# schematic.net
KiCad netlist of a schematic drawn in EAGLE
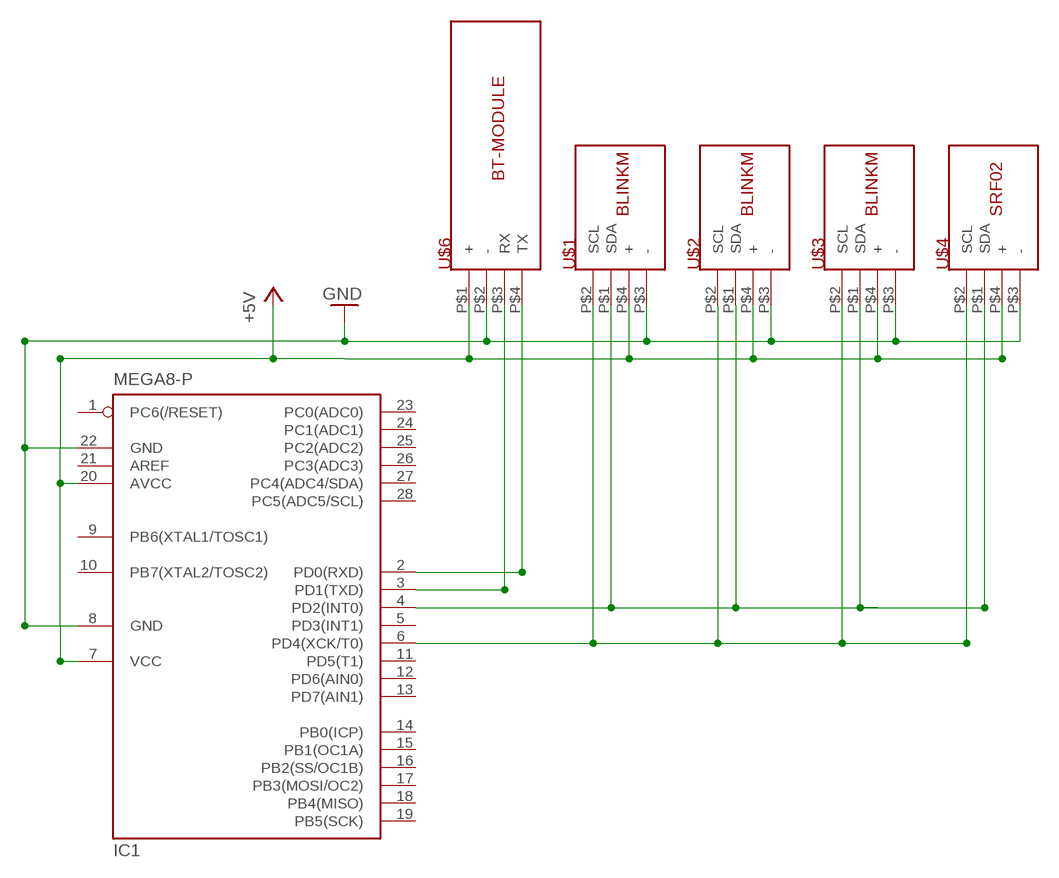
[diagram p0: schematic, sheet 1]

(export (version "E")
  (design (tool "Eeschema 10.0.6"))
  (components
    (comp (ref "IC1")
      (value "MEGA8-P")
      (footprint "eagle-import:DIL28-3")
      (libsource (lib "eagle-import") (part "MEGA8-P"))
    )
    (comp (ref "U$1")
      (value "BLINKM")
      (footprint "eagle-import:BLINKM")
      (libsource (lib "eagle-import") (part "BLINKM"))
    )
    (comp (ref "U$2")
      (value "BLINKM")
      (footprint "eagle-import:BLINKM")
      (libsource (lib "eagle-import") (part "BLINKM"))
    )
    (comp (ref "U$3")
      (value "BLINKM")
      (footprint "eagle-import:BLINKM")
      (libsource (lib "eagle-import") (part "BLINKM"))
    )
    (comp (ref "U$4")
      (value "SRF02")
      (footprint "eagle-import:BLINKM")
      (libsource (lib "eagle-import") (part "BLINKM"))
    )
    (comp (ref "U$6")
      (value "BT-MODULE")
      (footprint "eagle-import:BT-MODULE")
      (libsource (lib "eagle-import") (part "BT-MODULE"))
    )
  )
  (nets
    (net (code "1") (name "+5V") (class "Default")
      (node (ref "IC1") (pin "20") (pinfunction "AVCC_20") (pintype "power_in"))
      (node (ref "IC1") (pin "7") (pinfunction "VCC_7") (pintype "power_in"))
      (node (ref "U$1") (pin "P$4") (pinfunction "+_P$4") (pintype "bidirectional"))
      (node (ref "U$2") (pin "P$4") (pinfunction "+_P$4") (pintype "bidirectional"))
      (node (ref "U$3") (pin "P$4") (pinfunction "+_P$4") (pintype "bidirectional"))
      (node (ref "U$4") (pin "P$4") (pinfunction "+_P$4") (pintype "bidirectional"))
      (node (ref "U$6") (pin "P$1") (pinfunction "+_P$1") (pintype "bidirectional"))
    )
    (net (code "2") (name "GND") (class "Default")
      (node (ref "IC1") (pin "22") (pinfunction "GND_22") (pintype "power_in"))
      (node (ref "IC1") (pin "8") (pinfunction "GND_8") (pintype "power_in"))
      (node (ref "U$1") (pin "P$3") (pinfunction "-_P$3") (pintype "bidirectional"))
      (node (ref "U$2") (pin "P$3") (pinfunction "-_P$3") (pintype "bidirectional"))
      (node (ref "U$3") (pin "P$3") (pinfunction "-_P$3") (pintype "bidirectional"))
      (node (ref "U$4") (pin "P$3") (pinfunction "-_P$3") (pintype "bidirectional"))
      (node (ref "U$6") (pin "P$2") (pinfunction "-_P$2") (pintype "bidirectional"))
    )
    (net (code "3") (name "Net-(IC1-PD0(RXD))") (class "Default")
      (node (ref "IC1") (pin "2") (pinfunction "PD0(RXD)_2") (pintype "bidirectional"))
      (node (ref "U$6") (pin "P$4") (pinfunction "TX_P$4") (pintype "bidirectional"))
    )
    (net (code "4") (name "Net-(IC1-PD1(TXD))") (class "Default")
      (node (ref "IC1") (pin "3") (pinfunction "PD1(TXD)_3") (pintype "bidirectional"))
      (node (ref "U$6") (pin "P$3") (pinfunction "RX_P$3") (pintype "bidirectional"))
    )
    (net (code "5") (name "Net-(IC1-PD2(INT0))") (class "Default")
      (node (ref "IC1") (pin "4") (pinfunction "PD2(INT0)_4") (pintype "bidirectional"))
      (node (ref "U$1") (pin "P$1") (pinfunction "SDA_P$1") (pintype "bidirectional"))
      (node (ref "U$2") (pin "P$1") (pinfunction "SDA_P$1") (pintype "bidirectional"))
      (node (ref "U$3") (pin "P$1") (pinfunction "SDA_P$1") (pintype "bidirectional"))
      (node (ref "U$4") (pin "P$1") (pinfunction "SDA_P$1") (pintype "bidirectional"))
    )
    (net (code "6") (name "Net-(IC1-PD4(XCK{slash}T0))") (class "Default")
      (node (ref "IC1") (pin "6") (pinfunction "PD4(XCK/T0)_6") (pintype "bidirectional"))
      (node (ref "U$1") (pin "P$2") (pinfunction "SCL_P$2") (pintype "bidirectional"))
      (node (ref "U$2") (pin "P$2") (pinfunction "SCL_P$2") (pintype "bidirectional"))
      (node (ref "U$3") (pin "P$2") (pinfunction "SCL_P$2") (pintype "bidirectional"))
      (node (ref "U$4") (pin "P$2") (pinfunction "SCL_P$2") (pintype "bidirectional"))
    )
    (net (code "7") (name "unconnected-(IC1-AREF-Pad21)") (class "Default")
      (node (ref "IC1") (pin "21") (pinfunction "AREF_21") (pintype "passive"))
    )
    (net (code "8") (name "unconnected-(IC1-PB0(ICP)-Pad14)") (class "Default")
      (node (ref "IC1") (pin "14") (pinfunction "PB0(ICP)_14") (pintype "bidirectional"))
    )
    (net (code "9") (name "unconnected-(IC1-PB1(OC1A)-Pad15)") (class "Default")
      (node (ref "IC1") (pin "15") (pinfunction "PB1(OC1A)_15") (pintype "bidirectional"))
    )
    (net (code "10") (name "unconnected-(IC1-PB2(SS{slash}OC1B)-Pad16)") (class "Default")
      (node (ref "IC1") (pin "16") (pinfunction "PB2(SS/OC1B)_16") (pintype "bidirectional"))
    )
    (net (code "11") (name "unconnected-(IC1-PB3(MOSI{slash}OC2)-Pad17)") (class "Default")
      (node (ref "IC1") (pin "17") (pinfunction "PB3(MOSI/OC2)_17") (pintype "bidirectional"))
    )
    (net (code "12") (name "unconnected-(IC1-PB4(MISO)-Pad18)") (class "Default")
      (node (ref "IC1") (pin "18") (pinfunction "PB4(MISO)_18") (pintype "bidirectional"))
    )
    (net (code "13") (name "unconnected-(IC1-PB5(SCK)-Pad19)") (class "Default")
      (node (ref "IC1") (pin "19") (pinfunction "PB5(SCK)_19") (pintype "bidirectional"))
    )
    (net (code "14") (name "unconnected-(IC1-PB6(XTAL1{slash}TOSC1)-Pad9)") (class "Default")
      (node (ref "IC1") (pin "9") (pinfunction "PB6(XTAL1/TOSC1)_9") (pintype "bidirectional"))
    )
    (net (code "15") (name "unconnected-(IC1-PB7(XTAL2{slash}TOSC2)-Pad10)") (class "Default")
      (node (ref "IC1") (pin "10") (pinfunction "PB7(XTAL2/TOSC2)_10") (pintype "bidirectional"))
    )
    (net (code "16") (name "unconnected-(IC1-PC0(ADC0)-Pad23)") (class "Default")
      (node (ref "IC1") (pin "23") (pinfunction "PC0(ADC0)_23") (pintype "bidirectional"))
    )
    (net (code "17") (name "unconnected-(IC1-PC1(ADC1)-Pad24)") (class "Default")
      (node (ref "IC1") (pin "24") (pinfunction "PC1(ADC1)_24") (pintype "bidirectional"))
    )
    (net (code "18") (name "unconnected-(IC1-PC2(ADC2)-Pad25)") (class "Default")
      (node (ref "IC1") (pin "25") (pinfunction "PC2(ADC2)_25") (pintype "bidirectional"))
    )
    (net (code "19") (name "unconnected-(IC1-PC3(ADC3)-Pad26)") (class "Default")
      (node (ref "IC1") (pin "26") (pinfunction "PC3(ADC3)_26") (pintype "bidirectional"))
    )
    (net (code "20") (name "unconnected-(IC1-PC4(ADC4{slash}SDA)-Pad27)") (class "Default")
      (node (ref "IC1") (pin "27") (pinfunction "PC4(ADC4/SDA)_27") (pintype "bidirectional"))
    )
    (net (code "21") (name "unconnected-(IC1-PC5(ADC5{slash}SCL)-Pad28)") (class "Default")
      (node (ref "IC1") (pin "28") (pinfunction "PC5(ADC5/SCL)_28") (pintype "bidirectional"))
    )
    (net (code "22") (name "unconnected-(IC1-PC6({slash}RESET)-Pad1)") (class "Default")
      (node (ref "IC1") (pin "1") (pinfunction "PC6(/RESET)_1") (pintype "bidirectional"))
    )
    (net (code "23") (name "unconnected-(IC1-PD3(INT1)-Pad5)") (class "Default")
      (node (ref "IC1") (pin "5") (pinfunction "PD3(INT1)_5") (pintype "bidirectional"))
    )
    (net (code "24") (name "unconnected-(IC1-PD5(T1)-Pad11)") (class "Default")
      (node (ref "IC1") (pin "11") (pinfunction "PD5(T1)_11") (pintype "bidirectional"))
    )
    (net (code "25") (name "unconnected-(IC1-PD6(AIN0)-Pad12)") (class "Default")
      (node (ref "IC1") (pin "12") (pinfunction "PD6(AIN0)_12") (pintype "bidirectional"))
    )
    (net (code "26") (name "unconnected-(IC1-PD7(AIN1)-Pad13)") (class "Default")
      (node (ref "IC1") (pin "13") (pinfunction "PD7(AIN1)_13") (pintype "bidirectional"))
    )
  )
)
